# Schematic.net
KiCad netlist of a schematic drawn in Altium Designer
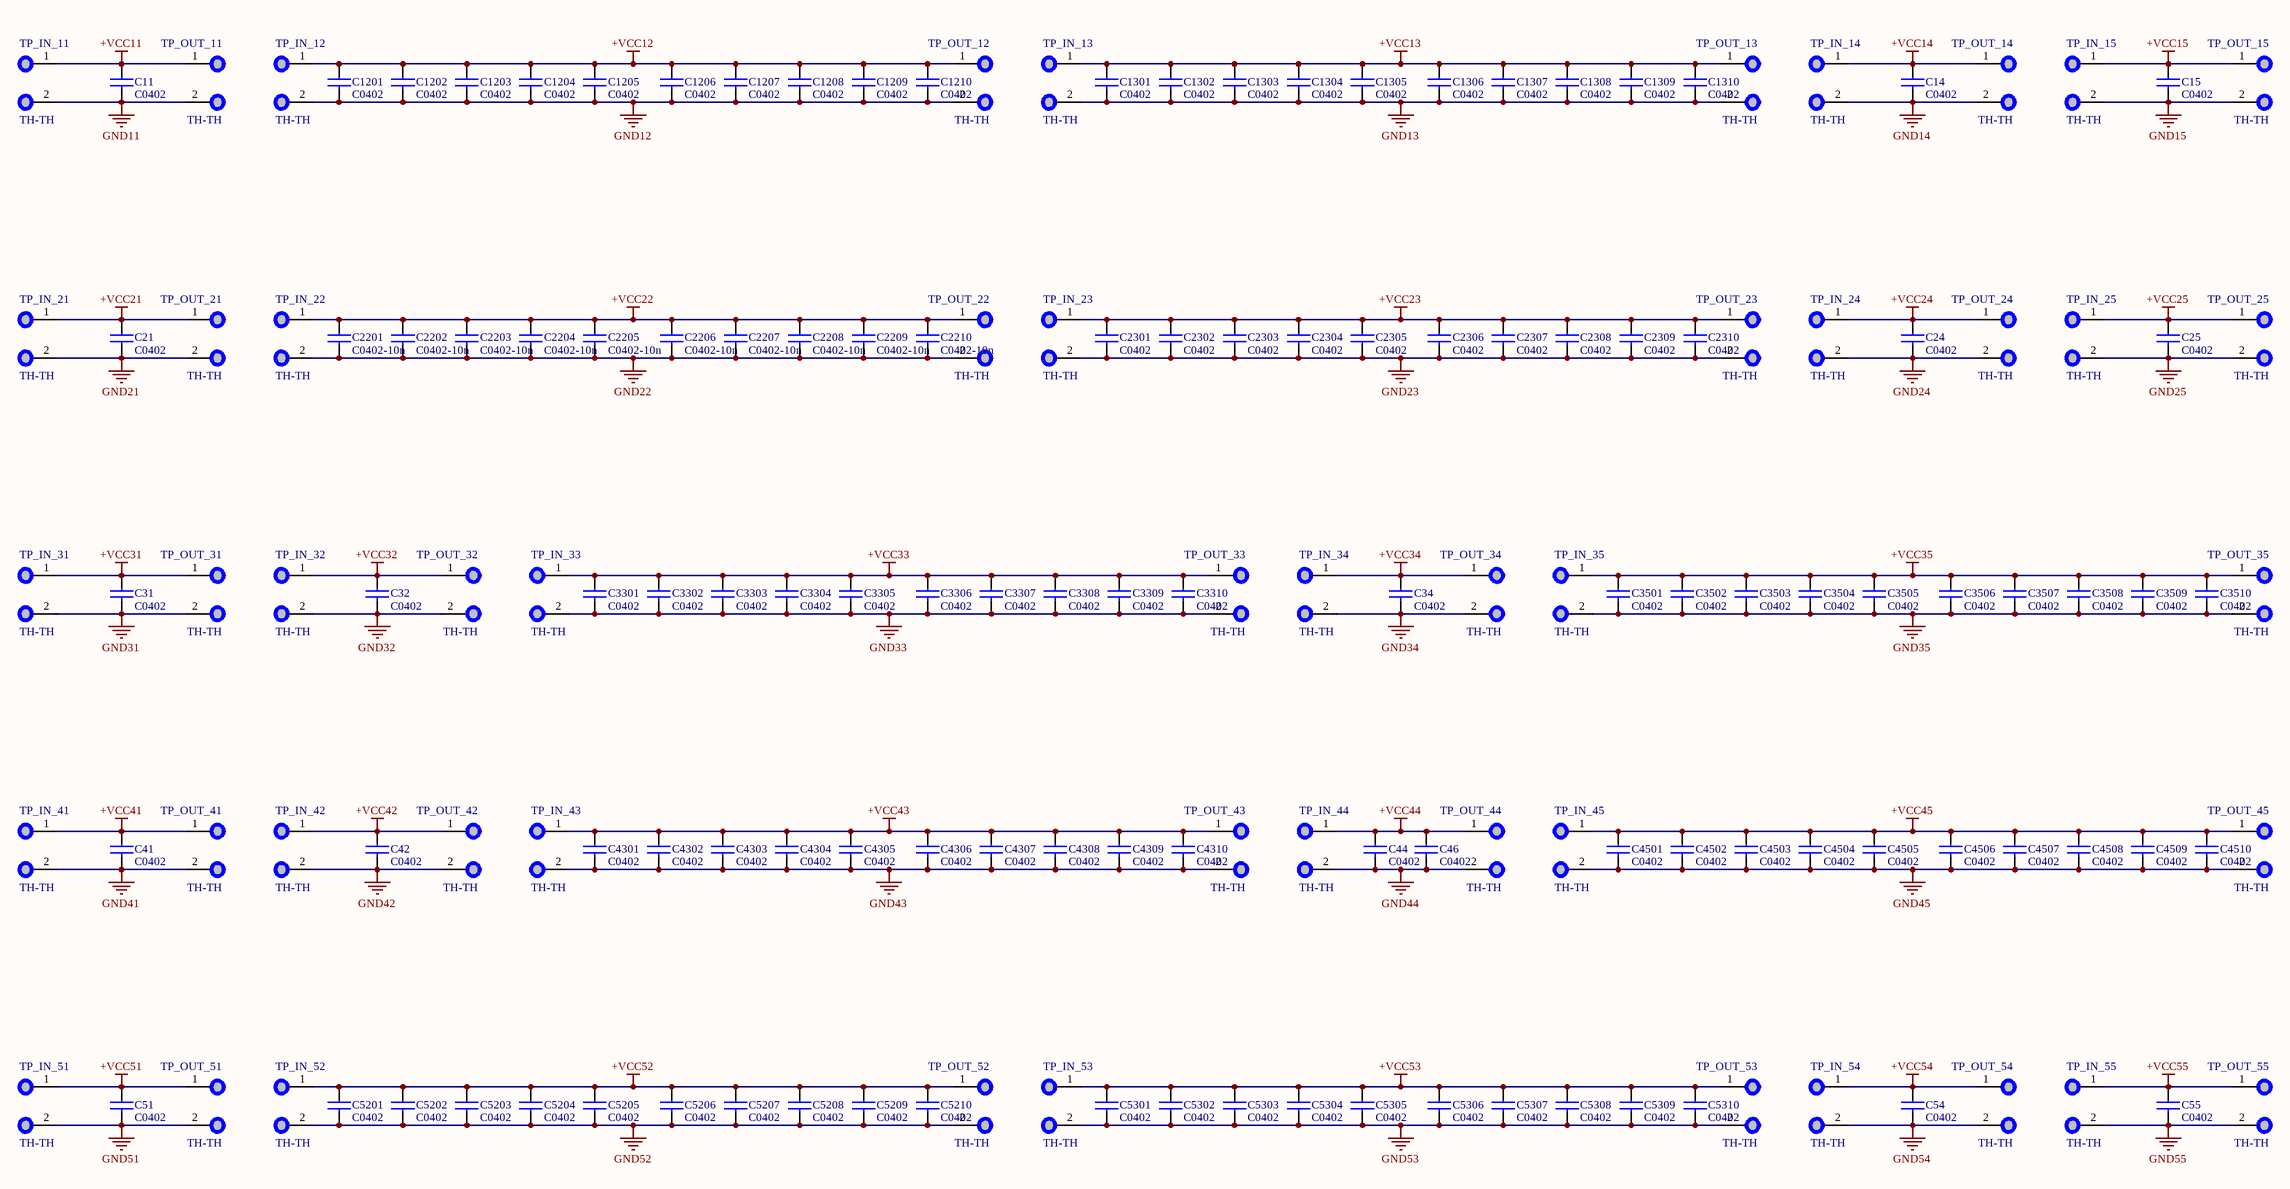
[diagram p0: Schematic.SchDoc]

(export (version "E")
  (design (tool "Eeschema 10.0.6"))
  (components
    (comp (ref "C11") (value "C0402") (footprint "C0402") (libsource (lib "Schlib") (part "CAP0402")))
    (comp (ref "C14") (value "C0402") (footprint "C0402") (libsource (lib "Schlib") (part "CAP0402")))
    (comp (ref "C15") (value "C0402") (footprint "C0402") (libsource (lib "Schlib") (part "CAP0402")))
    (comp (ref "C21") (value "C0402") (footprint "C0402") (libsource (lib "Schlib") (part "CAP0402")))
    (comp (ref "C24") (value "C0402") (footprint "C0402") (libsource (lib "Schlib") (part "CAP0402")))
    (comp (ref "C25") (value "C0402") (footprint "C0402") (libsource (lib "Schlib") (part "CAP0402")))
    (comp (ref "C31") (value "C0402") (footprint "C0402") (libsource (lib "Schlib") (part "CAP0402")))
    (comp (ref "C32") (value "C0402") (footprint "C0402") (libsource (lib "Schlib") (part "CAP0402")))
    (comp (ref "C34") (value "C0402") (footprint "C0402") (libsource (lib "Schlib") (part "CAP0402")))
    (comp (ref "C41") (value "C0402") (footprint "C0402") (libsource (lib "Schlib") (part "CAP0402")))
    (comp (ref "C42") (value "C0402") (footprint "C0402") (libsource (lib "Schlib") (part "CAP0402")))
    (comp (ref "C44") (value "C0402") (footprint "C0402") (libsource (lib "Schlib") (part "CAP0402")))
    (comp (ref "C46") (value "C0402") (footprint "C0402") (libsource (lib "Schlib") (part "CAP0402")))
    (comp (ref "C51") (value "C0402") (footprint "C0402") (libsource (lib "Schlib") (part "CAP0402")))
    (comp (ref "C54") (value "C0402") (footprint "C0402") (libsource (lib "Schlib") (part "CAP0402")))
    (comp (ref "C55") (value "C0402") (footprint "C0402") (libsource (lib "Schlib") (part "CAP0402")))
    (comp (ref "C1201") (value "C0402") (footprint "C0402") (libsource (lib "Schlib") (part "CAP0402")))
    (comp (ref "C1202") (value "C0402") (footprint "C0402") (libsource (lib "Schlib") (part "CAP0402")))
    (comp (ref "C1203") (value "C0402") (footprint "C0402") (libsource (lib "Schlib") (part "CAP0402")))
    (comp (ref "C1204") (value "C0402") (footprint "C0402") (libsource (lib "Schlib") (part "CAP0402")))
    (comp (ref "C1205") (value "C0402") (footprint "C0402") (libsource (lib "Schlib") (part "CAP0402")))
    (comp (ref "C1206") (value "C0402") (footprint "C0402") (libsource (lib "Schlib") (part "CAP0402")))
    (comp (ref "C1207") (value "C0402") (footprint "C0402") (libsource (lib "Schlib") (part "CAP0402")))
    (comp (ref "C1208") (value "C0402") (footprint "C0402") (libsource (lib "Schlib") (part "CAP0402")))
    (comp (ref "C1209") (value "C0402") (footprint "C0402") (libsource (lib "Schlib") (part "CAP0402")))
    (comp (ref "C1210") (value "C0402") (footprint "C0402") (libsource (lib "Schlib") (part "CAP0402")))
    (comp (ref "C1301") (value "C0402") (footprint "C0402") (libsource (lib "Schlib") (part "CAP0402")))
    (comp (ref "C1302") (value "C0402") (footprint "C0402") (libsource (lib "Schlib") (part "CAP0402")))
    (comp (ref "C1303") (value "C0402") (footprint "C0402") (libsource (lib "Schlib") (part "CAP0402")))
    (comp (ref "C1304") (value "C0402") (footprint "C0402") (libsource (lib "Schlib") (part "CAP0402")))
    (comp (ref "C1305") (value "C0402") (footprint "C0402") (libsource (lib "Schlib") (part "CAP0402")))
    (comp (ref "C1306") (value "C0402") (footprint "C0402") (libsource (lib "Schlib") (part "CAP0402")))
    (comp (ref "C1307") (value "C0402") (footprint "C0402") (libsource (lib "Schlib") (part "CAP0402")))
    (comp (ref "C1308") (value "C0402") (footprint "C0402") (libsource (lib "Schlib") (part "CAP0402")))
    (comp (ref "C1309") (value "C0402") (footprint "C0402") (libsource (lib "Schlib") (part "CAP0402")))
    (comp (ref "C1310") (value "C0402") (footprint "C0402") (libsource (lib "Schlib") (part "CAP0402")))
    (comp (ref "C2201") (value "C0402-10n") (footprint "C0402") (libsource (lib "Schlib") (part "CAP0402")))
    (comp (ref "C2202") (value "C0402-10n") (footprint "C0402") (libsource (lib "Schlib") (part "CAP0402")))
    (comp (ref "C2203") (value "C0402-10n") (footprint "C0402") (libsource (lib "Schlib") (part "CAP0402")))
    (comp (ref "C2204") (value "C0402-10n") (footprint "C0402") (libsource (lib "Schlib") (part "CAP0402")))
    (comp (ref "C2205") (value "C0402-10n") (footprint "C0402") (libsource (lib "Schlib") (part "CAP0402")))
    (comp (ref "C2206") (value "C0402-10n") (footprint "C0402") (libsource (lib "Schlib") (part "CAP0402")))
    (comp (ref "C2207") (value "C0402-10n") (footprint "C0402") (libsource (lib "Schlib") (part "CAP0402")))
    (comp (ref "C2208") (value "C0402-10n") (footprint "C0402") (libsource (lib "Schlib") (part "CAP0402")))
    (comp (ref "C2209") (value "C0402-10n") (footprint "C0402") (libsource (lib "Schlib") (part "CAP0402")))
    (comp (ref "C2210") (value "C0402-10n") (footprint "C0402") (libsource (lib "Schlib") (part "CAP0402")))
    (comp (ref "C2301") (value "C0402") (footprint "C0402") (libsource (lib "Schlib") (part "CAP0402")))
    (comp (ref "C2302") (value "C0402") (footprint "C0402") (libsource (lib "Schlib") (part "CAP0402")))
    (comp (ref "C2303") (value "C0402") (footprint "C0402") (libsource (lib "Schlib") (part "CAP0402")))
    (comp (ref "C2304") (value "C0402") (footprint "C0402") (libsource (lib "Schlib") (part "CAP0402")))
    (comp (ref "C2305") (value "C0402") (footprint "C0402") (libsource (lib "Schlib") (part "CAP0402")))
    (comp (ref "C2306") (value "C0402") (footprint "C0402") (libsource (lib "Schlib") (part "CAP0402")))
    (comp (ref "C2307") (value "C0402") (footprint "C0402") (libsource (lib "Schlib") (part "CAP0402")))
    (comp (ref "C2308") (value "C0402") (footprint "C0402") (libsource (lib "Schlib") (part "CAP0402")))
    (comp (ref "C2309") (value "C0402") (footprint "C0402") (libsource (lib "Schlib") (part "CAP0402")))
    (comp (ref "C2310") (value "C0402") (footprint "C0402") (libsource (lib "Schlib") (part "CAP0402")))
    (comp (ref "C3301") (value "C0402") (footprint "C0402") (libsource (lib "Schlib") (part "CAP0402")))
    (comp (ref "C3302") (value "C0402") (footprint "C0402") (libsource (lib "Schlib") (part "CAP0402")))
    (comp (ref "C3303") (value "C0402") (footprint "C0402") (libsource (lib "Schlib") (part "CAP0402")))
    (comp (ref "C3304") (value "C0402") (footprint "C0402") (libsource (lib "Schlib") (part "CAP0402")))
    (comp (ref "C3305") (value "C0402") (footprint "C0402") (libsource (lib "Schlib") (part "CAP0402")))
    (comp (ref "C3306") (value "C0402") (footprint "C0402") (libsource (lib "Schlib") (part "CAP0402")))
    (comp (ref "C3307") (value "C0402") (footprint "C0402") (libsource (lib "Schlib") (part "CAP0402")))
    (comp (ref "C3308") (value "C0402") (footprint "C0402") (libsource (lib "Schlib") (part "CAP0402")))
    (comp (ref "C3309") (value "C0402") (footprint "C0402") (libsource (lib "Schlib") (part "CAP0402")))
    (comp (ref "C3310") (value "C0402") (footprint "C0402") (libsource (lib "Schlib") (part "CAP0402")))
    (comp (ref "C3501") (value "C0402") (footprint "C0402") (libsource (lib "Schlib") (part "CAP0402")))
    (comp (ref "C3502") (value "C0402") (footprint "C0402") (libsource (lib "Schlib") (part "CAP0402")))
    (comp (ref "C3503") (value "C0402") (footprint "C0402") (libsource (lib "Schlib") (part "CAP0402")))
    (comp (ref "C3504") (value "C0402") (footprint "C0402") (libsource (lib "Schlib") (part "CAP0402")))
    (comp (ref "C3505") (value "C0402") (footprint "C0402") (libsource (lib "Schlib") (part "CAP0402")))
    (comp (ref "C3506") (value "C0402") (footprint "C0402") (libsource (lib "Schlib") (part "CAP0402")))
    (comp (ref "C3507") (value "C0402") (footprint "C0402") (libsource (lib "Schlib") (part "CAP0402")))
    (comp (ref "C3508") (value "C0402") (footprint "C0402") (libsource (lib "Schlib") (part "CAP0402")))
    (comp (ref "C3509") (value "C0402") (footprint "C0402") (libsource (lib "Schlib") (part "CAP0402")))
    (comp (ref "C3510") (value "C0402") (footprint "C0402") (libsource (lib "Schlib") (part "CAP0402")))
    (comp (ref "C4301") (value "C0402") (footprint "C0402") (libsource (lib "Schlib") (part "CAP0402")))
    (comp (ref "C4302") (value "C0402") (footprint "C0402") (libsource (lib "Schlib") (part "CAP0402")))
    (comp (ref "C4303") (value "C0402") (footprint "C0402") (libsource (lib "Schlib") (part "CAP0402")))
    (comp (ref "C4304") (value "C0402") (footprint "C0402") (libsource (lib "Schlib") (part "CAP0402")))
    (comp (ref "C4305") (value "C0402") (footprint "C0402") (libsource (lib "Schlib") (part "CAP0402")))
    (comp (ref "C4306") (value "C0402") (footprint "C0402") (libsource (lib "Schlib") (part "CAP0402")))
    (comp (ref "C4307") (value "C0402") (footprint "C0402") (libsource (lib "Schlib") (part "CAP0402")))
    (comp (ref "C4308") (value "C0402") (footprint "C0402") (libsource (lib "Schlib") (part "CAP0402")))
    (comp (ref "C4309") (value "C0402") (footprint "C0402") (libsource (lib "Schlib") (part "CAP0402")))
    (comp (ref "C4310") (value "C0402") (footprint "C0402") (libsource (lib "Schlib") (part "CAP0402")))
    (comp (ref "C4501") (value "C0402") (footprint "C0402") (libsource (lib "Schlib") (part "CAP0402")))
    (comp (ref "C4502") (value "C0402") (footprint "C0402") (libsource (lib "Schlib") (part "CAP0402")))
    (comp (ref "C4503") (value "C0402") (footprint "C0402") (libsource (lib "Schlib") (part "CAP0402")))
    (comp (ref "C4504") (value "C0402") (footprint "C0402") (libsource (lib "Schlib") (part "CAP0402")))
    (comp (ref "C4505") (value "C0402") (footprint "C0402") (libsource (lib "Schlib") (part "CAP0402")))
    (comp (ref "C4506") (value "C0402") (footprint "C0402") (libsource (lib "Schlib") (part "CAP0402")))
    (comp (ref "C4507") (value "C0402") (footprint "C0402") (libsource (lib "Schlib") (part "CAP0402")))
    (comp (ref "C4508") (value "C0402") (footprint "C0402") (libsource (lib "Schlib") (part "CAP0402")))
    (comp (ref "C4509") (value "C0402") (footprint "C0402") (libsource (lib "Schlib") (part "CAP0402")))
    (comp (ref "C4510") (value "C0402") (footprint "C0402") (libsource (lib "Schlib") (part "CAP0402")))
    (comp (ref "C5201") (value "C0402") (footprint "C0402") (libsource (lib "Schlib") (part "CAP0402")))
    (comp (ref "C5202") (value "C0402") (footprint "C0402") (libsource (lib "Schlib") (part "CAP0402")))
    (comp (ref "C5203") (value "C0402") (footprint "C0402") (libsource (lib "Schlib") (part "CAP0402")))
    (comp (ref "C5204") (value "C0402") (footprint "C0402") (libsource (lib "Schlib") (part "CAP0402")))
    (comp (ref "C5205") (value "C0402") (footprint "C0402") (libsource (lib "Schlib") (part "CAP0402")))
    (comp (ref "C5206") (value "C0402") (footprint "C0402") (libsource (lib "Schlib") (part "CAP0402")))
    (comp (ref "C5207") (value "C0402") (footprint "C0402") (libsource (lib "Schlib") (part "CAP0402")))
    (comp (ref "C5208") (value "C0402") (footprint "C0402") (libsource (lib "Schlib") (part "CAP0402")))
    (comp (ref "C5209") (value "C0402") (footprint "C0402") (libsource (lib "Schlib") (part "CAP0402")))
    (comp (ref "C5210") (value "C0402") (footprint "C0402") (libsource (lib "Schlib") (part "CAP0402")))
    (comp (ref "C5301") (value "C0402") (footprint "C0402") (libsource (lib "Schlib") (part "CAP0402")))
    (comp (ref "C5302") (value "C0402") (footprint "C0402") (libsource (lib "Schlib") (part "CAP0402")))
    (comp (ref "C5303") (value "C0402") (footprint "C0402") (libsource (lib "Schlib") (part "CAP0402")))
    (comp (ref "C5304") (value "C0402") (footprint "C0402") (libsource (lib "Schlib") (part "CAP0402")))
    (comp (ref "C5305") (value "C0402") (footprint "C0402") (libsource (lib "Schlib") (part "CAP0402")))
    (comp (ref "C5306") (value "C0402") (footprint "C0402") (libsource (lib "Schlib") (part "CAP0402")))
    (comp (ref "C5307") (value "C0402") (footprint "C0402") (libsource (lib "Schlib") (part "CAP0402")))
    (comp (ref "C5308") (value "C0402") (footprint "C0402") (libsource (lib "Schlib") (part "CAP0402")))
    (comp (ref "C5309") (value "C0402") (footprint "C0402") (libsource (lib "Schlib") (part "CAP0402")))
    (comp (ref "C5310") (value "C0402") (footprint "C0402") (libsource (lib "Schlib") (part "CAP0402")))
    (comp (ref "TP_IN_11")
      (value "TH-TH")
      (footprint "TP_TH_TH")
      (description "Testpoints TH - TH 1mm/0.3mm")
      (libsource (lib "Schlib") (part "TP_TH_TH"))
    )
    (comp (ref "TP_IN_12")
      (value "TH-TH")
      (footprint "TP_TH_TH")
      (description "Testpoints TH - TH 1mm/0.3mm")
      (libsource (lib "Schlib") (part "TP_TH_TH"))
    )
    (comp (ref "TP_IN_13")
      (value "TH-TH")
      (footprint "TP_TH_TH")
      (description "Testpoints TH - TH 1mm/0.3mm")
      (libsource (lib "Schlib") (part "TP_TH_TH"))
    )
    (comp (ref "TP_IN_14")
      (value "TH-TH")
      (footprint "TP_TH_TH")
      (description "Testpoints TH - TH 1mm/0.3mm")
      (libsource (lib "Schlib") (part "TP_TH_TH"))
    )
    (comp (ref "TP_IN_15")
      (value "TH-TH")
      (footprint "TP_TH_TH")
      (description "Testpoints TH - TH 1mm/0.3mm")
      (libsource (lib "Schlib") (part "TP_TH_TH"))
    )
    (comp (ref "TP_IN_21")
      (value "TH-TH")
      (footprint "TP_TH_TH")
      (description "Testpoints TH - TH 1mm/0.3mm")
      (libsource (lib "Schlib") (part "TP_TH_TH"))
    )
    (comp (ref "TP_IN_22")
      (value "TH-TH")
      (footprint "TP_TH_TH")
      (description "Testpoints TH - TH 1mm/0.3mm")
      (libsource (lib "Schlib") (part "TP_TH_TH"))
    )
    (comp (ref "TP_IN_23")
      (value "TH-TH")
      (footprint "TP_TH_TH")
      (description "Testpoints TH - TH 1mm/0.3mm")
      (libsource (lib "Schlib") (part "TP_TH_TH"))
    )
    (comp (ref "TP_IN_24")
      (value "TH-TH")
      (footprint "TP_TH_TH")
      (description "Testpoints TH - TH 1mm/0.3mm")
      (libsource (lib "Schlib") (part "TP_TH_TH"))
    )
    (comp (ref "TP_IN_25")
      (value "TH-TH")
      (footprint "TP_TH_TH")
      (description "Testpoints TH - TH 1mm/0.3mm")
      (libsource (lib "Schlib") (part "TP_TH_TH"))
    )
    (comp (ref "TP_IN_31")
      (value "TH-TH")
      (footprint "TP_TH_TH")
      (description "Testpoints TH - TH 1mm/0.3mm")
      (libsource (lib "Schlib") (part "TP_TH_TH"))
    )
    (comp (ref "TP_IN_32")
      (value "TH-TH")
      (footprint "TP_TH_TH")
      (description "Testpoints TH - TH 1mm/0.3mm")
      (libsource (lib "Schlib") (part "TP_TH_TH"))
    )
    (comp (ref "TP_IN_33")
      (value "TH-TH")
      (footprint "TP_TH_TH")
      (description "Testpoints TH - TH 1mm/0.3mm")
      (libsource (lib "Schlib") (part "TP_TH_TH"))
    )
    (comp (ref "TP_IN_34")
      (value "TH-TH")
      (footprint "TP_TH_TH")
      (description "Testpoints TH - TH 1mm/0.3mm")
      (libsource (lib "Schlib") (part "TP_TH_TH"))
    )
    (comp (ref "TP_IN_35")
      (value "TH-TH")
      (footprint "TP_TH_TH")
      (description "Testpoints TH - TH 1mm/0.3mm")
      (libsource (lib "Schlib") (part "TP_TH_TH"))
    )
    (comp (ref "TP_IN_41")
      (value "TH-TH")
      (footprint "TP_TH_TH")
      (description "Testpoints TH - TH 1mm/0.3mm")
      (libsource (lib "Schlib") (part "TP_TH_TH"))
    )
    (comp (ref "TP_IN_42")
      (value "TH-TH")
      (footprint "TP_TH_TH")
      (description "Testpoints TH - TH 1mm/0.3mm")
      (libsource (lib "Schlib") (part "TP_TH_TH"))
    )
    (comp (ref "TP_IN_43")
      (value "TH-TH")
      (footprint "TP_TH_TH")
      (description "Testpoints TH - TH 1mm/0.3mm")
      (libsource (lib "Schlib") (part "TP_TH_TH"))
    )
    (comp (ref "TP_IN_44")
      (value "TH-TH")
      (footprint "TP_TH_TH")
      (description "Testpoints TH - TH 1mm/0.3mm")
      (libsource (lib "Schlib") (part "TP_TH_TH"))
    )
    (comp (ref "TP_IN_45")
      (value "TH-TH")
      (footprint "TP_TH_TH")
      (description "Testpoints TH - TH 1mm/0.3mm")
      (libsource (lib "Schlib") (part "TP_TH_TH"))
    )
    (comp (ref "TP_IN_51")
      (value "TH-TH")
      (footprint "TP_TH_TH")
      (description "Testpoints TH - TH 1mm/0.3mm")
      (libsource (lib "Schlib") (part "TP_TH_TH"))
    )
    (comp (ref "TP_IN_52")
      (value "TH-TH")
      (footprint "TP_TH_TH")
      (description "Testpoints TH - TH 1mm/0.3mm")
      (libsource (lib "Schlib") (part "TP_TH_TH"))
    )
    (comp (ref "TP_IN_53")
      (value "TH-TH")
      (footprint "TP_TH_TH")
      (description "Testpoints TH - TH 1mm/0.3mm")
      (libsource (lib "Schlib") (part "TP_TH_TH"))
    )
    (comp (ref "TP_IN_54")
      (value "TH-TH")
      (footprint "TP_TH_TH")
      (description "Testpoints TH - TH 1mm/0.3mm")
      (libsource (lib "Schlib") (part "TP_TH_TH"))
    )
    (comp (ref "TP_IN_55")
      (value "TH-TH")
      (footprint "TP_TH_TH")
      (description "Testpoints TH - TH 1mm/0.3mm")
      (libsource (lib "Schlib") (part "TP_TH_TH"))
    )
    (comp (ref "TP_OUT_11")
      (value "TH-TH")
      (footprint "TP_TH_TH")
      (description "Testpoints TH - TH 1mm/0.3mm")
      (libsource (lib "Schlib") (part "TP_TH_TH"))
    )
    (comp (ref "TP_OUT_12")
      (value "TH-TH")
      (footprint "TP_TH_TH")
      (description "Testpoints TH - TH 1mm/0.3mm")
      (libsource (lib "Schlib") (part "TP_TH_TH"))
    )
    (comp (ref "TP_OUT_13")
      (value "TH-TH")
      (footprint "TP_TH_TH")
      (description "Testpoints TH - TH 1mm/0.3mm")
      (libsource (lib "Schlib") (part "TP_TH_TH"))
    )
    (comp (ref "TP_OUT_14")
      (value "TH-TH")
      (footprint "TP_TH_TH")
      (description "Testpoints TH - TH 1mm/0.3mm")
      (libsource (lib "Schlib") (part "TP_TH_TH"))
    )
    (comp (ref "TP_OUT_15")
      (value "TH-TH")
      (footprint "TP_TH_TH")
      (description "Testpoints TH - TH 1mm/0.3mm")
      (libsource (lib "Schlib") (part "TP_TH_TH"))
    )
    (comp (ref "TP_OUT_21")
      (value "TH-TH")
      (footprint "TP_TH_TH")
      (description "Testpoints TH - TH 1mm/0.3mm")
      (libsource (lib "Schlib") (part "TP_TH_TH"))
    )
    (comp (ref "TP_OUT_22")
      (value "TH-TH")
      (footprint "TP_TH_TH")
      (description "Testpoints TH - TH 1mm/0.3mm")
      (libsource (lib "Schlib") (part "TP_TH_TH"))
    )
    (comp (ref "TP_OUT_23")
      (value "TH-TH")
      (footprint "TP_TH_TH")
      (description "Testpoints TH - TH 1mm/0.3mm")
      (libsource (lib "Schlib") (part "TP_TH_TH"))
    )
    (comp (ref "TP_OUT_24")
      (value "TH-TH")
      (footprint "TP_TH_TH")
      (description "Testpoints TH - TH 1mm/0.3mm")
      (libsource (lib "Schlib") (part "TP_TH_TH"))
    )
    (comp (ref "TP_OUT_25")
      (value "TH-TH")
      (footprint "TP_TH_TH")
      (description "Testpoints TH - TH 1mm/0.3mm")
      (libsource (lib "Schlib") (part "TP_TH_TH"))
    )
    (comp (ref "TP_OUT_31")
      (value "TH-TH")
      (footprint "TP_TH_TH")
      (description "Testpoints TH - TH 1mm/0.3mm")
      (libsource (lib "Schlib") (part "TP_TH_TH"))
    )
    (comp (ref "TP_OUT_32")
      (value "TH-TH")
      (footprint "TP_TH_TH")
      (description "Testpoints TH - TH 1mm/0.3mm")
      (libsource (lib "Schlib") (part "TP_TH_TH"))
    )
    (comp (ref "TP_OUT_33")
      (value "TH-TH")
      (footprint "TP_TH_TH")
      (description "Testpoints TH - TH 1mm/0.3mm")
      (libsource (lib "Schlib") (part "TP_TH_TH"))
    )
    (comp (ref "TP_OUT_34")
      (value "TH-TH")
      (footprint "TP_TH_TH")
      (description "Testpoints TH - TH 1mm/0.3mm")
      (libsource (lib "Schlib") (part "TP_TH_TH"))
    )
    (comp (ref "TP_OUT_35")
      (value "TH-TH")
      (footprint "TP_TH_TH")
      (description "Testpoints TH - TH 1mm/0.3mm")
      (libsource (lib "Schlib") (part "TP_TH_TH"))
    )
    (comp (ref "TP_OUT_41")
      (value "TH-TH")
      (footprint "TP_TH_TH")
      (description "Testpoints TH - TH 1mm/0.3mm")
      (libsource (lib "Schlib") (part "TP_TH_TH"))
    )
    (comp (ref "TP_OUT_42")
      (value "TH-TH")
      (footprint "TP_TH_TH")
      (description "Testpoints TH - TH 1mm/0.3mm")
      (libsource (lib "Schlib") (part "TP_TH_TH"))
    )
    (comp (ref "TP_OUT_43")
      (value "TH-TH")
      (footprint "TP_TH_TH")
      (description "Testpoints TH - TH 1mm/0.3mm")
      (libsource (lib "Schlib") (part "TP_TH_TH"))
    )
    (comp (ref "TP_OUT_44")
      (value "TH-TH")
      (footprint "TP_TH_TH")
      (description "Testpoints TH - TH 1mm/0.3mm")
      (libsource (lib "Schlib") (part "TP_TH_TH"))
    )
    (comp (ref "TP_OUT_45")
      (value "TH-TH")
      (footprint "TP_TH_TH")
      (description "Testpoints TH - TH 1mm/0.3mm")
      (libsource (lib "Schlib") (part "TP_TH_TH"))
    )
    (comp (ref "TP_OUT_51")
      (value "TH-TH")
      (footprint "TP_TH_TH")
      (description "Testpoints TH - TH 1mm/0.3mm")
      (libsource (lib "Schlib") (part "TP_TH_TH"))
    )
    (comp (ref "TP_OUT_52")
      (value "TH-TH")
      (footprint "TP_TH_TH")
      (description "Testpoints TH - TH 1mm/0.3mm")
      (libsource (lib "Schlib") (part "TP_TH_TH"))
    )
    (comp (ref "TP_OUT_53")
      (value "TH-TH")
      (footprint "TP_TH_TH")
      (description "Testpoints TH - TH 1mm/0.3mm")
      (libsource (lib "Schlib") (part "TP_TH_TH"))
    )
    (comp (ref "TP_OUT_54")
      (value "TH-TH")
      (footprint "TP_TH_TH")
      (description "Testpoints TH - TH 1mm/0.3mm")
      (libsource (lib "Schlib") (part "TP_TH_TH"))
    )
    (comp (ref "TP_OUT_55")
      (value "TH-TH")
      (footprint "TP_TH_TH")
      (description "Testpoints TH - TH 1mm/0.3mm")
      (libsource (lib "Schlib") (part "TP_TH_TH"))
    )
  )
  (nets
    (net (code "1") (name "+VCC11") (class "Default")
      (node (ref "C11") (pin "1") (pinfunction "1_1") (pintype "passive"))
      (node (ref "TP_IN_11") (pin "1") (pinfunction "1_1") (pintype "passive"))
      (node (ref "TP_OUT_11") (pin "1") (pinfunction "1_1") (pintype "passive"))
    )
    (net (code "2") (name "+VCC12") (class "Default")
      (node (ref "C1201") (pin "1") (pinfunction "1_1") (pintype "passive"))
      (node (ref "C1202") (pin "1") (pinfunction "1_1") (pintype "passive"))
      (node (ref "C1203") (pin "1") (pinfunction "1_1") (pintype "passive"))
      (node (ref "C1204") (pin "1") (pinfunction "1_1") (pintype "passive"))
      (node (ref "C1205") (pin "1") (pinfunction "1_1") (pintype "passive"))
      (node (ref "C1206") (pin "1") (pinfunction "1_1") (pintype "passive"))
      (node (ref "C1207") (pin "1") (pinfunction "1_1") (pintype "passive"))
      (node (ref "C1208") (pin "1") (pinfunction "1_1") (pintype "passive"))
      (node (ref "C1209") (pin "1") (pinfunction "1_1") (pintype "passive"))
      (node (ref "C1210") (pin "1") (pinfunction "1_1") (pintype "passive"))
      (node (ref "TP_IN_12") (pin "1") (pinfunction "1_1") (pintype "passive"))
      (node (ref "TP_OUT_12") (pin "1") (pinfunction "1_1") (pintype "passive"))
    )
    (net (code "3") (name "+VCC13") (class "Default")
      (node (ref "C1301") (pin "1") (pinfunction "1_1") (pintype "passive"))
      (node (ref "C1302") (pin "1") (pinfunction "1_1") (pintype "passive"))
      (node (ref "C1303") (pin "1") (pinfunction "1_1") (pintype "passive"))
      (node (ref "C1304") (pin "1") (pinfunction "1_1") (pintype "passive"))
      (node (ref "C1305") (pin "1") (pinfunction "1_1") (pintype "passive"))
      (node (ref "C1306") (pin "1") (pinfunction "1_1") (pintype "passive"))
      (node (ref "C1307") (pin "1") (pinfunction "1_1") (pintype "passive"))
      (node (ref "C1308") (pin "1") (pinfunction "1_1") (pintype "passive"))
      (node (ref "C1309") (pin "1") (pinfunction "1_1") (pintype "passive"))
      (node (ref "C1310") (pin "1") (pinfunction "1_1") (pintype "passive"))
      (node (ref "TP_IN_13") (pin "1") (pinfunction "1_1") (pintype "passive"))
      (node (ref "TP_OUT_13") (pin "1") (pinfunction "1_1") (pintype "passive"))
    )
    (net (code "4") (name "+VCC14") (class "Default")
      (node (ref "C14") (pin "1") (pinfunction "1_1") (pintype "passive"))
      (node (ref "TP_IN_14") (pin "1") (pinfunction "1_1") (pintype "passive"))
      (node (ref "TP_OUT_14") (pin "1") (pinfunction "1_1") (pintype "passive"))
    )
    (net (code "5") (name "+VCC15") (class "Default")
      (node (ref "C15") (pin "1") (pinfunction "1_1") (pintype "passive"))
      (node (ref "TP_IN_15") (pin "1") (pinfunction "1_1") (pintype "passive"))
      (node (ref "TP_OUT_15") (pin "1") (pinfunction "1_1") (pintype "passive"))
    )
    (net (code "6") (name "+VCC21") (class "Default")
      (node (ref "C21") (pin "1") (pinfunction "1_1") (pintype "passive"))
      (node (ref "TP_IN_21") (pin "1") (pinfunction "1_1") (pintype "passive"))
      (node (ref "TP_OUT_21") (pin "1") (pinfunction "1_1") (pintype "passive"))
    )
    (net (code "7") (name "+VCC22") (class "Default")
      (node (ref "C2201") (pin "1") (pinfunction "1_1") (pintype "passive"))
      (node (ref "C2202") (pin "1") (pinfunction "1_1") (pintype "passive"))
      (node (ref "C2203") (pin "1") (pinfunction "1_1") (pintype "passive"))
      (node (ref "C2204") (pin "1") (pinfunction "1_1") (pintype "passive"))
      (node (ref "C2205") (pin "1") (pinfunction "1_1") (pintype "passive"))
      (node (ref "C2206") (pin "1") (pinfunction "1_1") (pintype "passive"))
      (node (ref "C2207") (pin "1") (pinfunction "1_1") (pintype "passive"))
      (node (ref "C2208") (pin "1") (pinfunction "1_1") (pintype "passive"))
      (node (ref "C2209") (pin "1") (pinfunction "1_1") (pintype "passive"))
      (node (ref "C2210") (pin "1") (pinfunction "1_1") (pintype "passive"))
      (node (ref "TP_IN_22") (pin "1") (pinfunction "1_1") (pintype "passive"))
      (node (ref "TP_OUT_22") (pin "1") (pinfunction "1_1") (pintype "passive"))
    )
    (net (code "8") (name "+VCC23") (class "Default")
      (node (ref "C2301") (pin "1") (pinfunction "1_1") (pintype "passive"))
      (node (ref "C2302") (pin "1") (pinfunction "1_1") (pintype "passive"))
      (node (ref "C2303") (pin "1") (pinfunction "1_1") (pintype "passive"))
      (node (ref "C2304") (pin "1") (pinfunction "1_1") (pintype "passive"))
      (node (ref "C2305") (pin "1") (pinfunction "1_1") (pintype "passive"))
      (node (ref "C2306") (pin "1") (pinfunction "1_1") (pintype "passive"))
      (node (ref "C2307") (pin "1") (pinfunction "1_1") (pintype "passive"))
      (node (ref "C2308") (pin "1") (pinfunction "1_1") (pintype "passive"))
      (node (ref "C2309") (pin "1") (pinfunction "1_1") (pintype "passive"))
      (node (ref "C2310") (pin "1") (pinfunction "1_1") (pintype "passive"))
      (node (ref "TP_IN_23") (pin "1") (pinfunction "1_1") (pintype "passive"))
      (node (ref "TP_OUT_23") (pin "1") (pinfunction "1_1") (pintype "passive"))
    )
    (net (code "9") (name "+VCC24") (class "Default")
      (node (ref "C24") (pin "1") (pinfunction "1_1") (pintype "passive"))
      (node (ref "TP_IN_24") (pin "1") (pinfunction "1_1") (pintype "passive"))
      (node (ref "TP_OUT_24") (pin "1") (pinfunction "1_1") (pintype "passive"))
    )
    (net (code "10") (name "+VCC25") (class "Default")
      (node (ref "C25") (pin "1") (pinfunction "1_1") (pintype "passive"))
      (node (ref "TP_IN_25") (pin "1") (pinfunction "1_1") (pintype "passive"))
      (node (ref "TP_OUT_25") (pin "1") (pinfunction "1_1") (pintype "passive"))
    )
    (net (code "11") (name "+VCC31") (class "Default")
      (node (ref "C31") (pin "1") (pinfunction "1_1") (pintype "passive"))
      (node (ref "TP_IN_31") (pin "1") (pinfunction "1_1") (pintype "passive"))
      (node (ref "TP_OUT_31") (pin "1") (pinfunction "1_1") (pintype "passive"))
    )
    (net (code "12") (name "+VCC32") (class "Default")
      (node (ref "C32") (pin "1") (pinfunction "1_1") (pintype "passive"))
      (node (ref "TP_IN_32") (pin "1") (pinfunction "1_1") (pintype "passive"))
      (node (ref "TP_OUT_32") (pin "1") (pinfunction "1_1") (pintype "passive"))
    )
    (net (code "13") (name "+VCC33") (class "Default")
      (node (ref "C3301") (pin "1") (pinfunction "1_1") (pintype "passive"))
      (node (ref "C3302") (pin "1") (pinfunction "1_1") (pintype "passive"))
      (node (ref "C3303") (pin "1") (pinfunction "1_1") (pintype "passive"))
      (node (ref "C3304") (pin "1") (pinfunction "1_1") (pintype "passive"))
      (node (ref "C3305") (pin "1") (pinfunction "1_1") (pintype "passive"))
      (node (ref "C3306") (pin "1") (pinfunction "1_1") (pintype "passive"))
      (node (ref "C3307") (pin "1") (pinfunction "1_1") (pintype "passive"))
      (node (ref "C3308") (pin "1") (pinfunction "1_1") (pintype "passive"))
      (node (ref "C3309") (pin "1") (pinfunction "1_1") (pintype "passive"))
      (node (ref "C3310") (pin "1") (pinfunction "1_1") (pintype "passive"))
      (node (ref "TP_IN_33") (pin "1") (pinfunction "1_1") (pintype "passive"))
      (node (ref "TP_OUT_33") (pin "1") (pinfunction "1_1") (pintype "passive"))
    )
    (net (code "14") (name "+VCC34") (class "Default")
      (node (ref "C34") (pin "1") (pinfunction "1_1") (pintype "passive"))
      (node (ref "TP_IN_34") (pin "1") (pinfunction "1_1") (pintype "passive"))
      (node (ref "TP_OUT_34") (pin "1") (pinfunction "1_1") (pintype "passive"))
    )
    (net (code "15") (name "+VCC35") (class "Default")
      (node (ref "C3501") (pin "1") (pinfunction "1_1") (pintype "passive"))
      (node (ref "C3502") (pin "1") (pinfunction "1_1") (pintype "passive"))
      (node (ref "C3503") (pin "1") (pinfunction "1_1") (pintype "passive"))
      (node (ref "C3504") (pin "1") (pinfunction "1_1") (pintype "passive"))
      (node (ref "C3505") (pin "1") (pinfunction "1_1") (pintype "passive"))
      (node (ref "C3506") (pin "1") (pinfunction "1_1") (pintype "passive"))
      (node (ref "C3507") (pin "1") (pinfunction "1_1") (pintype "passive"))
      (node (ref "C3508") (pin "1") (pinfunction "1_1") (pintype "passive"))
      (node (ref "C3509") (pin "1") (pinfunction "1_1") (pintype "passive"))
      (node (ref "C3510") (pin "1") (pinfunction "1_1") (pintype "passive"))
      (node (ref "TP_IN_35") (pin "1") (pinfunction "1_1") (pintype "passive"))
      (node (ref "TP_OUT_35") (pin "1") (pinfunction "1_1") (pintype "passive"))
    )
    (net (code "16") (name "+VCC41") (class "Default")
      (node (ref "C41") (pin "1") (pinfunction "1_1") (pintype "passive"))
      (node (ref "TP_IN_41") (pin "1") (pinfunction "1_1") (pintype "passive"))
      (node (ref "TP_OUT_41") (pin "1") (pinfunction "1_1") (pintype "passive"))
    )
    (net (code "17") (name "+VCC42") (class "Default")
      (node (ref "C42") (pin "1") (pinfunction "1_1") (pintype "passive"))
      (node (ref "TP_IN_42") (pin "1") (pinfunction "1_1") (pintype "passive"))
      (node (ref "TP_OUT_42") (pin "1") (pinfunction "1_1") (pintype "passive"))
    )
    (net (code "18") (name "+VCC43") (class "Default")
      (node (ref "C4301") (pin "1") (pinfunction "1_1") (pintype "passive"))
      (node (ref "C4302") (pin "1") (pinfunction "1_1") (pintype "passive"))
      (node (ref "C4303") (pin "1") (pinfunction "1_1") (pintype "passive"))
      (node (ref "C4304") (pin "1") (pinfunction "1_1") (pintype "passive"))
      (node (ref "C4305") (pin "1") (pinfunction "1_1") (pintype "passive"))
      (node (ref "C4306") (pin "1") (pinfunction "1_1") (pintype "passive"))
      (node (ref "C4307") (pin "1") (pinfunction "1_1") (pintype "passive"))
      (node (ref "C4308") (pin "1") (pinfunction "1_1") (pintype "passive"))
      (node (ref "C4309") (pin "1") (pinfunction "1_1") (pintype "passive"))
      (node (ref "C4310") (pin "1") (pinfunction "1_1") (pintype "passive"))
      (node (ref "TP_IN_43") (pin "1") (pinfunction "1_1") (pintype "passive"))
      (node (ref "TP_OUT_43") (pin "1") (pinfunction "1_1") (pintype "passive"))
    )
    (net (code "19") (name "+VCC44") (class "Default")
      (node (ref "C44") (pin "1") (pinfunction "1_1") (pintype "passive"))
      (node (ref "C46") (pin "1") (pinfunction "1_1") (pintype "passive"))
      (node (ref "TP_IN_44") (pin "1") (pinfunction "1_1") (pintype "passive"))
      (node (ref "TP_OUT_44") (pin "1") (pinfunction "1_1") (pintype "passive"))
    )
    (net (code "20") (name "+VCC45") (class "Default")
      (node (ref "C4501") (pin "1") (pinfunction "1_1") (pintype "passive"))
      (node (ref "C4502") (pin "1") (pinfunction "1_1") (pintype "passive"))
      (node (ref "C4503") (pin "1") (pinfunction "1_1") (pintype "passive"))
      (node (ref "C4504") (pin "1") (pinfunction "1_1") (pintype "passive"))
      (node (ref "C4505") (pin "1") (pinfunction "1_1") (pintype "passive"))
      (node (ref "C4506") (pin "1") (pinfunction "1_1") (pintype "passive"))
      (node (ref "C4507") (pin "1") (pinfunction "1_1") (pintype "passive"))
      (node (ref "C4508") (pin "1") (pinfunction "1_1") (pintype "passive"))
      (node (ref "C4509") (pin "1") (pinfunction "1_1") (pintype "passive"))
      (node (ref "C4510") (pin "1") (pinfunction "1_1") (pintype "passive"))
      (node (ref "TP_IN_45") (pin "1") (pinfunction "1_1") (pintype "passive"))
      (node (ref "TP_OUT_45") (pin "1") (pinfunction "1_1") (pintype "passive"))
    )
    (net (code "21") (name "+VCC51") (class "Default")
      (node (ref "C51") (pin "1") (pinfunction "1_1") (pintype "passive"))
      (node (ref "TP_IN_51") (pin "1") (pinfunction "1_1") (pintype "passive"))
      (node (ref "TP_OUT_51") (pin "1") (pinfunction "1_1") (pintype "passive"))
    )
    (net (code "22") (name "+VCC52") (class "Default")
      (node (ref "C5201") (pin "1") (pinfunction "1_1") (pintype "passive"))
      (node (ref "C5202") (pin "1") (pinfunction "1_1") (pintype "passive"))
      (node (ref "C5203") (pin "1") (pinfunction "1_1") (pintype "passive"))
      (node (ref "C5204") (pin "1") (pinfunction "1_1") (pintype "passive"))
      (node (ref "C5205") (pin "1") (pinfunction "1_1") (pintype "passive"))
      (node (ref "C5206") (pin "1") (pinfunction "1_1") (pintype "passive"))
      (node (ref "C5207") (pin "1") (pinfunction "1_1") (pintype "passive"))
      (node (ref "C5208") (pin "1") (pinfunction "1_1") (pintype "passive"))
      (node (ref "C5209") (pin "1") (pinfunction "1_1") (pintype "passive"))
      (node (ref "C5210") (pin "1") (pinfunction "1_1") (pintype "passive"))
      (node (ref "TP_IN_52") (pin "1") (pinfunction "1_1") (pintype "passive"))
      (node (ref "TP_OUT_52") (pin "1") (pinfunction "1_1") (pintype "passive"))
    )
    (net (code "23") (name "+VCC53") (class "Default")
      (node (ref "C5301") (pin "1") (pinfunction "1_1") (pintype "passive"))
      (node (ref "C5302") (pin "1") (pinfunction "1_1") (pintype "passive"))
      (node (ref "C5303") (pin "1") (pinfunction "1_1") (pintype "passive"))
      (node (ref "C5304") (pin "1") (pinfunction "1_1") (pintype "passive"))
      (node (ref "C5305") (pin "1") (pinfunction "1_1") (pintype "passive"))
      (node (ref "C5306") (pin "1") (pinfunction "1_1") (pintype "passive"))
      (node (ref "C5307") (pin "1") (pinfunction "1_1") (pintype "passive"))
      (node (ref "C5308") (pin "1") (pinfunction "1_1") (pintype "passive"))
      (node (ref "C5309") (pin "1") (pinfunction "1_1") (pintype "passive"))
      (node (ref "C5310") (pin "1") (pinfunction "1_1") (pintype "passive"))
      (node (ref "TP_IN_53") (pin "1") (pinfunction "1_1") (pintype "passive"))
      (node (ref "TP_OUT_53") (pin "1") (pinfunction "1_1") (pintype "passive"))
    )
    (net (code "24") (name "+VCC54") (class "Default")
      (node (ref "C54") (pin "1") (pinfunction "1_1") (pintype "passive"))
      (node (ref "TP_IN_54") (pin "1") (pinfunction "1_1") (pintype "passive"))
      (node (ref "TP_OUT_54") (pin "1") (pinfunction "1_1") (pintype "passive"))
    )
    (net (code "25") (name "+VCC55") (class "Default")
      (node (ref "C55") (pin "1") (pinfunction "1_1") (pintype "passive"))
      (node (ref "TP_IN_55") (pin "1") (pinfunction "1_1") (pintype "passive"))
      (node (ref "TP_OUT_55") (pin "1") (pinfunction "1_1") (pintype "passive"))
    )
    (net (code "26") (name "GND11") (class "Default")
      (node (ref "C11") (pin "2") (pinfunction "2_2") (pintype "passive"))
      (node (ref "TP_IN_11") (pin "2") (pinfunction "2_2") (pintype "passive"))
      (node (ref "TP_OUT_11") (pin "2") (pinfunction "2_2") (pintype "passive"))
    )
    (net (code "27") (name "GND12") (class "Default")
      (node (ref "C1201") (pin "2") (pinfunction "2_2") (pintype "passive"))
      (node (ref "C1202") (pin "2") (pinfunction "2_2") (pintype "passive"))
      (node (ref "C1203") (pin "2") (pinfunction "2_2") (pintype "passive"))
      (node (ref "C1204") (pin "2") (pinfunction "2_2") (pintype "passive"))
      (node (ref "C1205") (pin "2") (pinfunction "2_2") (pintype "passive"))
      (node (ref "C1206") (pin "2") (pinfunction "2_2") (pintype "passive"))
      (node (ref "C1207") (pin "2") (pinfunction "2_2") (pintype "passive"))
      (node (ref "C1208") (pin "2") (pinfunction "2_2") (pintype "passive"))
      (node (ref "C1209") (pin "2") (pinfunction "2_2") (pintype "passive"))
      (node (ref "C1210") (pin "2") (pinfunction "2_2") (pintype "passive"))
      (node (ref "TP_IN_12") (pin "2") (pinfunction "2_2") (pintype "passive"))
      (node (ref "TP_OUT_12") (pin "2") (pinfunction "2_2") (pintype "passive"))
    )
    (net (code "28") (name "GND13") (class "Default")
      (node (ref "C1301") (pin "2") (pinfunction "2_2") (pintype "passive"))
      (node (ref "C1302") (pin "2") (pinfunction "2_2") (pintype "passive"))
      (node (ref "C1303") (pin "2") (pinfunction "2_2") (pintype "passive"))
      (node (ref "C1304") (pin "2") (pinfunction "2_2") (pintype "passive"))
      (node (ref "C1305") (pin "2") (pinfunction "2_2") (pintype "passive"))
      (node (ref "C1306") (pin "2") (pinfunction "2_2") (pintype "passive"))
      (node (ref "C1307") (pin "2") (pinfunction "2_2") (pintype "passive"))
      (node (ref "C1308") (pin "2") (pinfunction "2_2") (pintype "passive"))
      (node (ref "C1309") (pin "2") (pinfunction "2_2") (pintype "passive"))
      (node (ref "C1310") (pin "2") (pinfunction "2_2") (pintype "passive"))
      (node (ref "TP_IN_13") (pin "2") (pinfunction "2_2") (pintype "passive"))
      (node (ref "TP_OUT_13") (pin "2") (pinfunction "2_2") (pintype "passive"))
    )
    (net (code "29") (name "GND14") (class "Default")
      (node (ref "C14") (pin "2") (pinfunction "2_2") (pintype "passive"))
      (node (ref "TP_IN_14") (pin "2") (pinfunction "2_2") (pintype "passive"))
      (node (ref "TP_OUT_14") (pin "2") (pinfunction "2_2") (pintype "passive"))
    )
    (net (code "30") (name "GND15") (class "Default")
      (node (ref "C15") (pin "2") (pinfunction "2_2") (pintype "passive"))
      (node (ref "TP_IN_15") (pin "2") (pinfunction "2_2") (pintype "passive"))
      (node (ref "TP_OUT_15") (pin "2") (pinfunction "2_2") (pintype "passive"))
    )
    (net (code "31") (name "GND21") (class "Default")
      (node (ref "C21") (pin "2") (pinfunction "2_2") (pintype "passive"))
      (node (ref "TP_IN_21") (pin "2") (pinfunction "2_2") (pintype "passive"))
      (node (ref "TP_OUT_21") (pin "2") (pinfunction "2_2") (pintype "passive"))
    )
    (net (code "32") (name "GND22") (class "Default")
      (node (ref "C2201") (pin "2") (pinfunction "2_2") (pintype "passive"))
      (node (ref "C2202") (pin "2") (pinfunction "2_2") (pintype "passive"))
      (node (ref "C2203") (pin "2") (pinfunction "2_2") (pintype "passive"))
      (node (ref "C2204") (pin "2") (pinfunction "2_2") (pintype "passive"))
      (node (ref "C2205") (pin "2") (pinfunction "2_2") (pintype "passive"))
      (node (ref "C2206") (pin "2") (pinfunction "2_2") (pintype "passive"))
      (node (ref "C2207") (pin "2") (pinfunction "2_2") (pintype "passive"))
      (node (ref "C2208") (pin "2") (pinfunction "2_2") (pintype "passive"))
      (node (ref "C2209") (pin "2") (pinfunction "2_2") (pintype "passive"))
      (node (ref "C2210") (pin "2") (pinfunction "2_2") (pintype "passive"))
      (node (ref "TP_IN_22") (pin "2") (pinfunction "2_2") (pintype "passive"))
      (node (ref "TP_OUT_22") (pin "2") (pinfunction "2_2") (pintype "passive"))
    )
    (net (code "33") (name "GND23") (class "Default")
      (node (ref "C2301") (pin "2") (pinfunction "2_2") (pintype "passive"))
      (node (ref "C2302") (pin "2") (pinfunction "2_2") (pintype "passive"))
      (node (ref "C2303") (pin "2") (pinfunction "2_2") (pintype "passive"))
      (node (ref "C2304") (pin "2") (pinfunction "2_2") (pintype "passive"))
      (node (ref "C2305") (pin "2") (pinfunction "2_2") (pintype "passive"))
      (node (ref "C2306") (pin "2") (pinfunction "2_2") (pintype "passive"))
      (node (ref "C2307") (pin "2") (pinfunction "2_2") (pintype "passive"))
      (node (ref "C2308") (pin "2") (pinfunction "2_2") (pintype "passive"))
      (node (ref "C2309") (pin "2") (pinfunction "2_2") (pintype "passive"))
      (node (ref "C2310") (pin "2") (pinfunction "2_2") (pintype "passive"))
      (node (ref "TP_IN_23") (pin "2") (pinfunction "2_2") (pintype "passive"))
      (node (ref "TP_OUT_23") (pin "2") (pinfunction "2_2") (pintype "passive"))
    )
    (net (code "34") (name "GND24") (class "Default")
      (node (ref "C24") (pin "2") (pinfunction "2_2") (pintype "passive"))
      (node (ref "TP_IN_24") (pin "2") (pinfunction "2_2") (pintype "passive"))
      (node (ref "TP_OUT_24") (pin "2") (pinfunction "2_2") (pintype "passive"))
    )
    (net (code "35") (name "GND25") (class "Default")
      (node (ref "C25") (pin "2") (pinfunction "2_2") (pintype "passive"))
      (node (ref "TP_IN_25") (pin "2") (pinfunction "2_2") (pintype "passive"))
      (node (ref "TP_OUT_25") (pin "2") (pinfunction "2_2") (pintype "passive"))
    )
    (net (code "36") (name "GND31") (class "Default")
      (node (ref "C31") (pin "2") (pinfunction "2_2") (pintype "passive"))
      (node (ref "TP_IN_31") (pin "2") (pinfunction "2_2") (pintype "passive"))
      (node (ref "TP_OUT_31") (pin "2") (pinfunction "2_2") (pintype "passive"))
    )
    (net (code "37") (name "GND32") (class "Default")
      (node (ref "C32") (pin "2") (pinfunction "2_2") (pintype "passive"))
      (node (ref "TP_IN_32") (pin "2") (pinfunction "2_2") (pintype "passive"))
      (node (ref "TP_OUT_32") (pin "2") (pinfunction "2_2") (pintype "passive"))
    )
    (net (code "38") (name "GND33") (class "Default")
      (node (ref "C3301") (pin "2") (pinfunction "2_2") (pintype "passive"))
      (node (ref "C3302") (pin "2") (pinfunction "2_2") (pintype "passive"))
      (node (ref "C3303") (pin "2") (pinfunction "2_2") (pintype "passive"))
      (node (ref "C3304") (pin "2") (pinfunction "2_2") (pintype "passive"))
      (node (ref "C3305") (pin "2") (pinfunction "2_2") (pintype "passive"))
      (node (ref "C3306") (pin "2") (pinfunction "2_2") (pintype "passive"))
      (node (ref "C3307") (pin "2") (pinfunction "2_2") (pintype "passive"))
      (node (ref "C3308") (pin "2") (pinfunction "2_2") (pintype "passive"))
      (node (ref "C3309") (pin "2") (pinfunction "2_2") (pintype "passive"))
      (node (ref "C3310") (pin "2") (pinfunction "2_2") (pintype "passive"))
      (node (ref "TP_IN_33") (pin "2") (pinfunction "2_2") (pintype "passive"))
      (node (ref "TP_OUT_33") (pin "2") (pinfunction "2_2") (pintype "passive"))
    )
    (net (code "39") (name "GND34") (class "Default")
      (node (ref "C34") (pin "2") (pinfunction "2_2") (pintype "passive"))
      (node (ref "TP_IN_34") (pin "2") (pinfunction "2_2") (pintype "passive"))
      (node (ref "TP_OUT_34") (pin "2") (pinfunction "2_2") (pintype "passive"))
    )
    (net (code "40") (name "GND35") (class "Default")
      (node (ref "C3501") (pin "2") (pinfunction "2_2") (pintype "passive"))
      (node (ref "C3502") (pin "2") (pinfunction "2_2") (pintype "passive"))
      (node (ref "C3503") (pin "2") (pinfunction "2_2") (pintype "passive"))
      (node (ref "C3504") (pin "2") (pinfunction "2_2") (pintype "passive"))
      (node (ref "C3505") (pin "2") (pinfunction "2_2") (pintype "passive"))
      (node (ref "C3506") (pin "2") (pinfunction "2_2") (pintype "passive"))
      (node (ref "C3507") (pin "2") (pinfunction "2_2") (pintype "passive"))
      (node (ref "C3508") (pin "2") (pinfunction "2_2") (pintype "passive"))
      (node (ref "C3509") (pin "2") (pinfunction "2_2") (pintype "passive"))
      (node (ref "C3510") (pin "2") (pinfunction "2_2") (pintype "passive"))
      (node (ref "TP_IN_35") (pin "2") (pinfunction "2_2") (pintype "passive"))
      (node (ref "TP_OUT_35") (pin "2") (pinfunction "2_2") (pintype "passive"))
    )
    (net (code "41") (name "GND41") (class "Default")
      (node (ref "C41") (pin "2") (pinfunction "2_2") (pintype "passive"))
      (node (ref "TP_IN_41") (pin "2") (pinfunction "2_2") (pintype "passive"))
      (node (ref "TP_OUT_41") (pin "2") (pinfunction "2_2") (pintype "passive"))
    )
    (net (code "42") (name "GND42") (class "Default")
      (node (ref "C42") (pin "2") (pinfunction "2_2") (pintype "passive"))
      (node (ref "TP_IN_42") (pin "2") (pinfunction "2_2") (pintype "passive"))
      (node (ref "TP_OUT_42") (pin "2") (pinfunction "2_2") (pintype "passive"))
    )
    (net (code "43") (name "GND43") (class "Default")
      (node (ref "C4301") (pin "2") (pinfunction "2_2") (pintype "passive"))
      (node (ref "C4302") (pin "2") (pinfunction "2_2") (pintype "passive"))
      (node (ref "C4303") (pin "2") (pinfunction "2_2") (pintype "passive"))
      (node (ref "C4304") (pin "2") (pinfunction "2_2") (pintype "passive"))
      (node (ref "C4305") (pin "2") (pinfunction "2_2") (pintype "passive"))
      (node (ref "C4306") (pin "2") (pinfunction "2_2") (pintype "passive"))
      (node (ref "C4307") (pin "2") (pinfunction "2_2") (pintype "passive"))
      (node (ref "C4308") (pin "2") (pinfunction "2_2") (pintype "passive"))
      (node (ref "C4309") (pin "2") (pinfunction "2_2") (pintype "passive"))
      (node (ref "C4310") (pin "2") (pinfunction "2_2") (pintype "passive"))
      (node (ref "TP_IN_43") (pin "2") (pinfunction "2_2") (pintype "passive"))
      (node (ref "TP_OUT_43") (pin "2") (pinfunction "2_2") (pintype "passive"))
    )
    (net (code "44") (name "GND44") (class "Default")
      (node (ref "C44") (pin "2") (pinfunction "2_2") (pintype "passive"))
      (node (ref "C46") (pin "2") (pinfunction "2_2") (pintype "passive"))
      (node (ref "TP_IN_44") (pin "2") (pinfunction "2_2") (pintype "passive"))
      (node (ref "TP_OUT_44") (pin "2") (pinfunction "2_2") (pintype "passive"))
    )
    (net (code "45") (name "GND45") (class "Default")
      (node (ref "C4501") (pin "2") (pinfunction "2_2") (pintype "passive"))
      (node (ref "C4502") (pin "2") (pinfunction "2_2") (pintype "passive"))
      (node (ref "C4503") (pin "2") (pinfunction "2_2") (pintype "passive"))
      (node (ref "C4504") (pin "2") (pinfunction "2_2") (pintype "passive"))
      (node (ref "C4505") (pin "2") (pinfunction "2_2") (pintype "passive"))
      (node (ref "C4506") (pin "2") (pinfunction "2_2") (pintype "passive"))
      (node (ref "C4507") (pin "2") (pinfunction "2_2") (pintype "passive"))
      (node (ref "C4508") (pin "2") (pinfunction "2_2") (pintype "passive"))
      (node (ref "C4509") (pin "2") (pinfunction "2_2") (pintype "passive"))
      (node (ref "C4510") (pin "2") (pinfunction "2_2") (pintype "passive"))
      (node (ref "TP_IN_45") (pin "2") (pinfunction "2_2") (pintype "passive"))
      (node (ref "TP_OUT_45") (pin "2") (pinfunction "2_2") (pintype "passive"))
    )
    (net (code "46") (name "GND51") (class "Default")
      (node (ref "C51") (pin "2") (pinfunction "2_2") (pintype "passive"))
      (node (ref "TP_IN_51") (pin "2") (pinfunction "2_2") (pintype "passive"))
      (node (ref "TP_OUT_51") (pin "2") (pinfunction "2_2") (pintype "passive"))
    )
    (net (code "47") (name "GND52") (class "Default")
      (node (ref "C5201") (pin "2") (pinfunction "2_2") (pintype "passive"))
      (node (ref "C5202") (pin "2") (pinfunction "2_2") (pintype "passive"))
      (node (ref "C5203") (pin "2") (pinfunction "2_2") (pintype "passive"))
      (node (ref "C5204") (pin "2") (pinfunction "2_2") (pintype "passive"))
      (node (ref "C5205") (pin "2") (pinfunction "2_2") (pintype "passive"))
      (node (ref "C5206") (pin "2") (pinfunction "2_2") (pintype "passive"))
      (node (ref "C5207") (pin "2") (pinfunction "2_2") (pintype "passive"))
      (node (ref "C5208") (pin "2") (pinfunction "2_2") (pintype "passive"))
      (node (ref "C5209") (pin "2") (pinfunction "2_2") (pintype "passive"))
      (node (ref "C5210") (pin "2") (pinfunction "2_2") (pintype "passive"))
      (node (ref "TP_IN_52") (pin "2") (pinfunction "2_2") (pintype "passive"))
      (node (ref "TP_OUT_52") (pin "2") (pinfunction "2_2") (pintype "passive"))
    )
    (net (code "48") (name "GND53") (class "Default")
      (node (ref "C5301") (pin "2") (pinfunction "2_2") (pintype "passive"))
      (node (ref "C5302") (pin "2") (pinfunction "2_2") (pintype "passive"))
      (node (ref "C5303") (pin "2") (pinfunction "2_2") (pintype "passive"))
      (node (ref "C5304") (pin "2") (pinfunction "2_2") (pintype "passive"))
      (node (ref "C5305") (pin "2") (pinfunction "2_2") (pintype "passive"))
      (node (ref "C5306") (pin "2") (pinfunction "2_2") (pintype "passive"))
      (node (ref "C5307") (pin "2") (pinfunction "2_2") (pintype "passive"))
      (node (ref "C5308") (pin "2") (pinfunction "2_2") (pintype "passive"))
      (node (ref "C5309") (pin "2") (pinfunction "2_2") (pintype "passive"))
      (node (ref "C5310") (pin "2") (pinfunction "2_2") (pintype "passive"))
      (node (ref "TP_IN_53") (pin "2") (pinfunction "2_2") (pintype "passive"))
      (node (ref "TP_OUT_53") (pin "2") (pinfunction "2_2") (pintype "passive"))
    )
    (net (code "49") (name "GND54") (class "Default")
      (node (ref "C54") (pin "2") (pinfunction "2_2") (pintype "passive"))
      (node (ref "TP_IN_54") (pin "2") (pinfunction "2_2") (pintype "passive"))
      (node (ref "TP_OUT_54") (pin "2") (pinfunction "2_2") (pintype "passive"))
    )
    (net (code "50") (name "GND55") (class "Default")
      (node (ref "C55") (pin "2") (pinfunction "2_2") (pintype "passive"))
      (node (ref "TP_IN_55") (pin "2") (pinfunction "2_2") (pintype "passive"))
      (node (ref "TP_OUT_55") (pin "2") (pinfunction "2_2") (pintype "passive"))
    )
  )
)
